# NANO33BLE_SENSE.net
KiCad netlist of a schematic drawn in Altium Designer
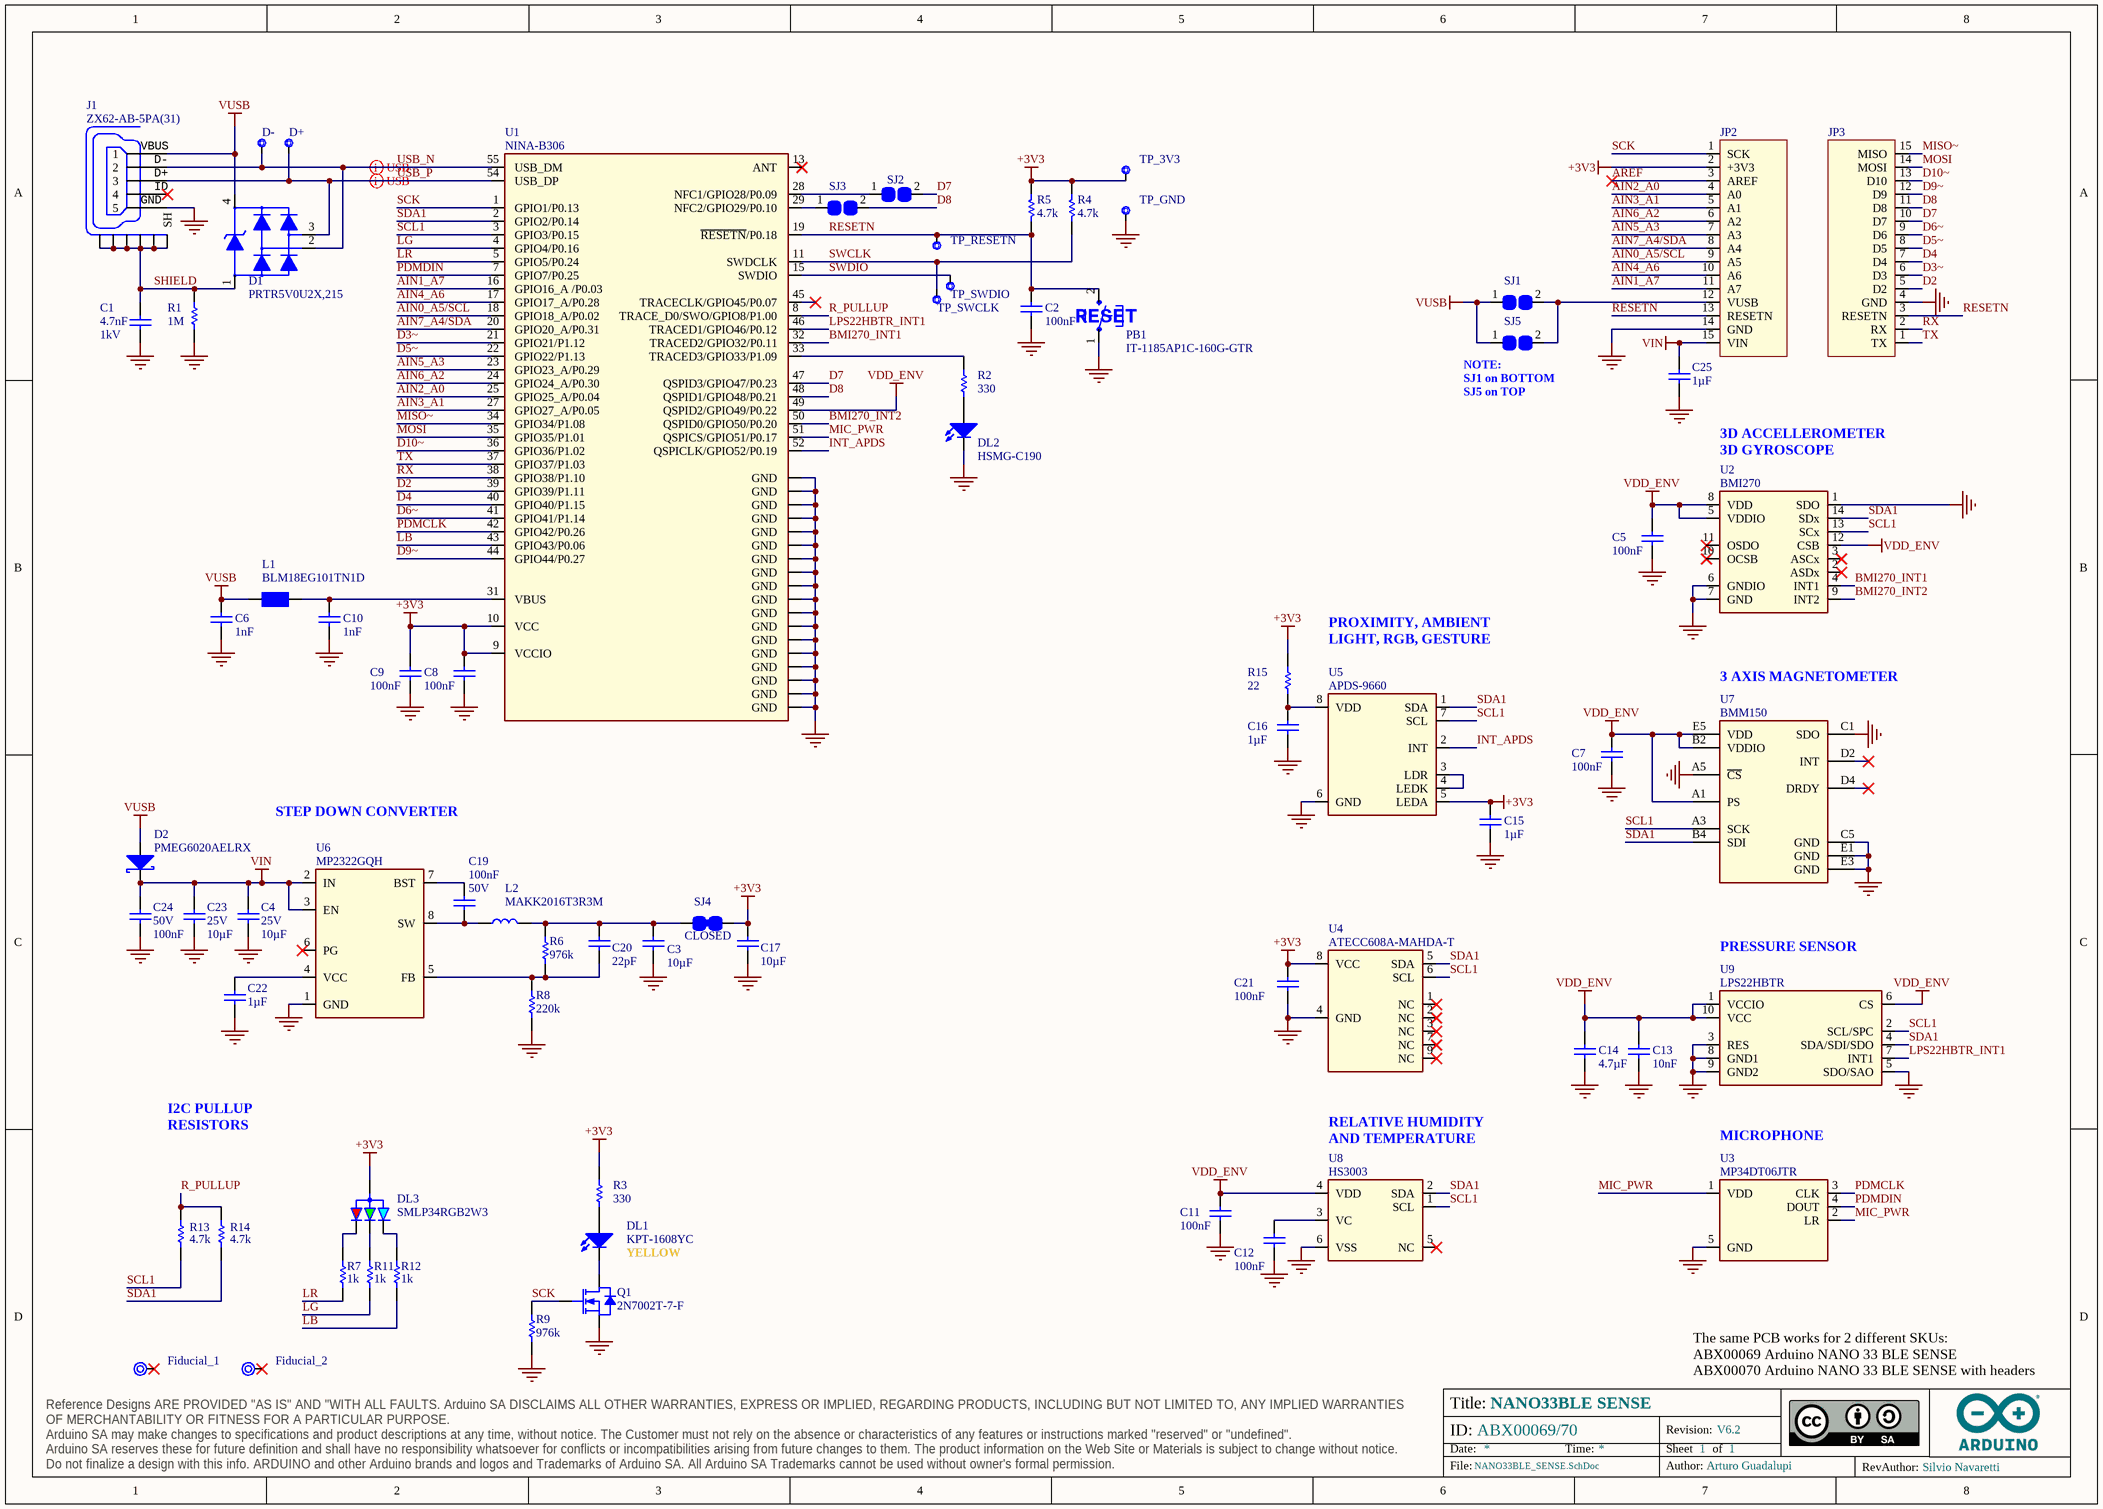
[diagram p0: NANO33BLE_SENSE.SchDoc]

(export (version "E")
  (design (tool "Eeschema 10.0.6"))
  (components
    (comp (ref "C1")
      (value "4.7nF")
      (footprint "CAP-0805")
      (description "CAP CHIP 0805 4.7nF 1000V X7R 10%")
      (fields
        (field (name "MANUFACTURER") "KEMET")
        (field (name "VOLTAGE") "1kV")
        (field (name "TOLERANCE") "10%")
      )
      (libsource (lib "Clean") (part "CAP"))
    )
    (comp (ref "C2")
      (value "100nF")
      (footprint "CAP-0402")
      (description "CAP CHIP 0402 100nF 50V X5R 10%")
      (fields (field (name "MANUFACTURER") "Murata") (field (name "PART NUMBER") "GRM155R61H104KE19D"))
      (libsource (lib "Clean") (part "CAP"))
    )
    (comp (ref "C3")
      (value "10µF")
      (footprint "CAP-0603")
      (description "CAP CHIP 0603 10uF 25V X5R 20%")
      (fields (field (name "VOLTAGE") "25V") (field (name "PART NUMBER") "GRM188R61E106MA73J"))
      (libsource (lib "Clean") (part "CAP"))
    )
    (comp (ref "C4")
      (value "10µF")
      (footprint "CAP-0603")
      (description "CAP CHIP 0603 10uF 25V X5R 20%")
      (fields
        (field (name "VOLTAGE") "25V")
        (field (name "PART NUMBER") "GRM188R61E106MA73J")
        (field (name "TOLERANCE") "20%")
      )
      (libsource (lib "Clean") (part "CAP"))
    )
    (comp (ref "C5")
      (value "100nF")
      (footprint "CAP-0402")
      (description "CAP CHIP 0402 100nF 16V X7R 10%")
      (fields (field (name "MANUFACTURER") "KEMET") (field (name "PART NUMBER") "C0402C104K4RACTU"))
      (libsource (lib "Clean") (part "CAP"))
    )
    (comp (ref "C6")
      (value "1nF")
      (footprint "CAP-0402")
      (description "CAP CHIP 0402 1nF 50V X7R 10%")
      (fields (field (name "MANUFACTURER") "KEMET") (field (name "PART NUMBER") "C0402C100K5RACTU"))
      (libsource (lib "Clean") (part "CAP"))
    )
    (comp (ref "C7")
      (value "100nF")
      (footprint "CAP-0402")
      (description "CAP CHIP 0402 100nF 50V X5R 10%")
      (fields (field (name "VOLTAGE") "50V") (field (name "TOLERANCE") "10%"))
      (libsource (lib "Clean") (part "CAP"))
    )
    (comp (ref "C8")
      (value "100nF")
      (footprint "CAP-0402")
      (description "CAP CHIP 0402 100nF 50V X5R 10%")
      (fields (field (name "MANUFACTURER") "Murata") (field (name "PART NUMBER") "GRM155R61H104KE19D"))
      (libsource (lib "Clean") (part "CAP"))
    )
    (comp (ref "C9")
      (value "100nF")
      (footprint "CAP-0402")
      (description "CAP CHIP 0402 100nF 50V X5R 10%")
      (fields (field (name "MANUFACTURER") "Murata") (field (name "PART NUMBER") "GRM155R61H104KE19D"))
      (libsource (lib "Clean") (part "CAP"))
    )
    (comp (ref "C10")
      (value "1nF")
      (footprint "CAP-0402")
      (description "CAP CHIP 0402 1nF 50V X7R 10%")
      (fields (field (name "MANUFACTURER") "KEMET") (field (name "PART NUMBER") "C0402C100K5RACTU"))
      (libsource (lib "Clean") (part "CAP"))
    )
    (comp (ref "C11")
      (value "100nF")
      (footprint "CAP-0402")
      (description "CAP CHIP 0402 100nF 50V X5R 10%")
      (fields (field (name "MANUFACTURER") "Murata") (field (name "PART NUMBER") "GRM155R61H104KE19D"))
      (libsource (lib "Clean") (part "CAP"))
    )
    (comp (ref "C12")
      (value "100nF")
      (footprint "CAP-0402")
      (description "CAP CHIP 0402 100nF 50V X5R 10%")
      (fields (field (name "MANUFACTURER") "Murata") (field (name "PART NUMBER") "GRM155R61H104KE19D"))
      (libsource (lib "Clean") (part "CAP"))
    )
    (comp (ref "C13")
      (value "10nF")
      (footprint "CAP-0402")
      (description "CAP CHIP 0402 10nF 50V X7R 10%")
      (fields (field (name "MANUFACTURER") "KEMET") (field (name "VOLTAGE") "50V"))
      (libsource (lib "Clean") (part "CAP"))
    )
    (comp (ref "C14")
      (value "4.7µF")
      (footprint "CAP-0402")
      (description "CAP CHIP 0402 4.7uF 6V3 X5R 20%")
      (fields (field (name "MANUFACTURER") "Murata") (field (name "PART NUMBER") "GRM155R60J475ME47D"))
      (libsource (lib "Clean") (part "CAP"))
    )
    (comp (ref "C15")
      (value "1µF")
      (footprint "CAP-0402")
      (description "CAP CHIP 0402 1uF 10V X5R 10%")
      (fields (field (name "MANUFACTURER") "KEMET") (field (name "VOLTAGE") "10V"))
      (libsource (lib "Clean") (part "CAP"))
    )
    (comp (ref "C16")
      (value "1µF")
      (footprint "CAP-0402")
      (description "CAP CHIP 0402 1uF 10V X5R 10%")
      (fields (field (name "MANUFACTURER") "KEMET") (field (name "VOLTAGE") "10V"))
      (libsource (lib "Clean") (part "CAP"))
    )
    (comp (ref "C17")
      (value "10µF")
      (footprint "CAP-0603")
      (description "CAP CHIP 0603 10uF 25V X5R 20%")
      (fields (field (name "VOLTAGE") "25V") (field (name "PART NUMBER") "GRM188R61E106MA73J"))
      (libsource (lib "Clean") (part "CAP"))
    )
    (comp (ref "C19")
      (value "100nF")
      (footprint "CAP-0402")
      (description "CAP CHIP 0402 100nF 50V X5R 10%")
      (fields
        (field (name "VOLTAGE") "50V")
        (field (name "PART NUMBER") "GRM155R61H104KE19D")
        (field (name "MANUFACTURER") "Murata")
      )
      (libsource (lib "Clean") (part "CAP"))
    )
    (comp (ref "C20")
      (value "22pF")
      (footprint "CAP-0402")
      (description "CAP CHIP 0402 22pF 50V C0G 5%")
      (fields (field (name "TOLERANCE") "5%") (field (name "PART NUMBER") "C0402C220J5GAC7411"))
      (libsource (lib "Clean") (part "CAP"))
    )
    (comp (ref "C21")
      (value "100nF")
      (footprint "CAP-0402")
      (description "CAP CHIP 0402 100nF 50V X5R 10%")
      (fields (field (name "MANUFACTURER") "Murata") (field (name "PART NUMBER") "GRM155R61H104KE19D"))
      (libsource (lib "Clean") (part "CAP"))
    )
    (comp (ref "C22")
      (value "1µF")
      (footprint "CAP-0402")
      (description "CAP CHIP 0402 1uF 10V X5R 10%")
      (fields (field (name "TOLERANCE") "10%") (field (name "MANUFACTURER") "KEMET"))
      (libsource (lib "Clean") (part "CAP"))
    )
    (comp (ref "C23")
      (value "10µF")
      (footprint "CAP-0603")
      (description "CAP CHIP 0603 10uF 25V X5R 20%")
      (fields
        (field (name "VOLTAGE") "25V")
        (field (name "PART NUMBER") "GRM188R61E106MA73J")
        (field (name "TOLERANCE") "20%")
      )
      (libsource (lib "Clean") (part "CAP"))
    )
    (comp (ref "C24")
      (value "100nF")
      (footprint "CAP-0402")
      (description "CAP CHIP 0402 100nF 50V X5R 10%")
      (fields
        (field (name "MANUFACTURER") "Murata")
        (field (name "PART NUMBER") "GRM155R61H104KE19D")
        (field (name "VOLTAGE") "50V")
      )
      (libsource (lib "Clean") (part "CAP"))
    )
    (comp (ref "C25")
      (value "1µF")
      (footprint "CAP-0402")
      (description "CAP CHIP 0402 1uF 10V X5R 10%")
      (fields (field (name "MANUFACTURER") "KEMET") (field (name "PART NUMBER") "C0402C105K8PACTU"))
      (libsource (lib "Clean") (part "CAP"))
    )
    (comp (ref "D+")
      (value "CMP-018-0005-A.3")
      (footprint "TP-1.00MM")
      (description "Test point 1.00mm")
      (libsource (lib "Clean") (part "TESTPOINT"))
    )
    (comp (ref "D-")
      (value "CMP-018-0005-A.3")
      (footprint "TP-1.00MM")
      (description "Test point 1.00mm")
      (libsource (lib "Clean") (part "TESTPOINT"))
    )
    (comp (ref "D1")
      (value "PRTR5V0U2X,215")
      (footprint "SOT190P230X110-4N")
      (description "TVS ARRAY 4LIN.8kV 1pF SOT143B")
      (fields (field (name "MANUFACTURER") "Nexperia"))
      (libsource (lib "Clean") (part "PRTR5V0U2X,215"))
    )
    (comp (ref "D2")
      (value "PMEG6020AELRX")
      (footprint "SOD123-1")
      (description "DIODE SCHOTTKY SMD 2A 60V SOD123FL")
      (fields (field (name "MANUFACTURER") "Nexperia"))
      (libsource (lib "Clean") (part "PMEG6020AELRX"))
    )
    (comp (ref "DL1")
      (value "KPT-1608YC")
      (footprint "LEDC1608X80N-AK")
      (description "LED SMD 0603 GIA588   8mcd 120^")
      (fields (field (name "MANUFACTURER") "Kingbright"))
      (libsource (lib "Clean") (part "LED"))
    )
    (comp (ref "DL2")
      (value "HSMG-C190")
      (footprint "LEDC1608X80N-AK")
      (description "LED SMD 0603 GREEN/568 15mcd 120^")
      (fields (field (name "MANUFACTURER") "Broadcom"))
      (libsource (lib "Clean") (part "LED"))
    )
    (comp (ref "DL3")
      (value "SMLP34RGB2W3")
      (footprint "SMLP34RGB2W")
      (description "LED RGB DIFFUSED PICOLED SMD")
      (fields (field (name "MANUFACTURER") "ROHM Semiconductor"))
      (libsource (lib "Clean") (part "SMLP34RGB2W3"))
    )
    (comp (ref "Fiducial_1")
      (value "Fiducial mark 1mm with 2mm solder")
      (footprint "Fiducial mark 1mm with circle-Footprint-1")
      (libsource (lib "Clean") (part "Fiducial mark 1mm with circle"))
    )
    (comp (ref "Fiducial_2")
      (value "Fiducial mark 1mm with 2mm solder")
      (footprint "Fiducial mark 1mm with circle-Footprint-1")
      (libsource (lib "Clean") (part "Fiducial mark 1mm with circle"))
    )
    (comp (ref "J1")
      (value "ZX62-AB-5PA(31)")
      (footprint "ZX62-AB-5PA")
      (description "CONN USB MICRO F/90^ SMD TipoAB 5x1")
      (fields (field (name "MANUFACTURER") "Hirose"))
      (libsource (lib "Clean") (part "ZX62-AB-5PA(31)"))
    )
    (comp (ref "JP2")
      (value "PINHD-1X15-NANO-ANALOG-CASTELLATED")
      (footprint "PINHD-1X14_5VF")
      (description "CONN THD SOCKET F/1/D 15V JANALOG NANO-TYPE CASTELLATED")
      (libsource (lib "Clean") (part "PINHD-1X15-NANO-ANALOG-CASTELLATED"))
    )
    (comp (ref "JP3")
      (value "PINHD-1X15-NANO-DIGITAL")
      (footprint "PINHD-1X14_5VF")
      (description "CONN THD SOCKET F/1/D 15V JDIGITAL NANO-TYPE CASTELLATED")
      (libsource (lib "Clean") (part "PINHD-1X15-NANO-DIGITAL"))
    )
    (comp (ref "L1")
      (value "BLM18EG101TN1D")
      (footprint "L-0603")
      (description "FERRITE SMD 0603 45mOHM 2A")
      (fields
        (field (name "MANUFACTURER") "Murata")
        (field (name "PART NUMBER") "BLM18EG101TN1D")
        (field (name "TOLERANCE") "25%")
      )
      (libsource (lib "Clean") (part "Ferrite"))
    )
    (comp (ref "L2")
      (value "MAKK2016T3R3M")
      (footprint "MAKK2016T3R3M-Footprint-1")
      (description "IND CHIP 0806 3.3 uH 20% 1.2A")
      (fields (field (name "TOLERANCE") "20%") (field (name "MANUFACTURER") "Taiyo Yuden"))
      (libsource (lib "Clean") (part "Inductor"))
    )
    (comp (ref "PB1")
      (value "IT-1185AP1C-160G-GTR")
      (footprint "C&K_PTS820_NO_HOLES-1")
      (description "PUSHBUTTON WHITE NO ANCHORS")
      (fields (field (name "MANUFACTURER") "Switronic"))
      (libsource (lib "Clean") (part "PTS820"))
    )
    (comp (ref "Q1")
      (value "2N7002T-7-F")
      (footprint "SOT523")
      (description "MOSFET N-CH 60V 115mA SOT523")
      (fields (field (name "MANUFACTURER") "Diodes Inc."))
      (libsource (lib "Clean") (part "NMOS"))
    )
    (comp (ref "R1")
      (value "1M")
      (footprint "RES-0402")
      (description "RES CHIP 0402 1M 1% 1/16W")
      (fields (field (name "MANUFACTURER") "Vishay") (field (name "POWER") "63mW"))
      (libsource (lib "Clean") (part "RES"))
    )
    (comp (ref "R2")
      (value "330")
      (footprint "RES-0402")
      (description "RES CHIP 0402 330R 5% 1/16W")
      (fields (field (name "MANUFACTURER") "Vishay") (field (name "POWER") "63mW"))
      (libsource (lib "Clean") (part "RES"))
    )
    (comp (ref "R3")
      (value "330")
      (footprint "RES-0402")
      (description "RES CHIP 0402 330R 5% 1/16W")
      (fields (field (name "MANUFACTURER") "Vishay") (field (name "POWER") "63mW"))
      (libsource (lib "Clean") (part "RES"))
    )
    (comp (ref "R4")
      (value "4.7k")
      (footprint "RES-0402")
      (description "RES CHIP 0402 4K7 1% 1/16W")
      (fields (field (name "MANUFACTURER") "Yageo") (field (name "PART NUMBER") "RC0402FR-074K7L"))
      (libsource (lib "Clean") (part "RES"))
    )
    (comp (ref "R5")
      (value "4.7k")
      (footprint "RES-0402")
      (description "RES CHIP 0402 4K7 1% 1/16W")
      (fields (field (name "MANUFACTURER") "Yageo") (field (name "PART NUMBER") "RC0402FR-074K7L"))
      (libsource (lib "Clean") (part "RES"))
    )
    (comp (ref "R6")
      (value "976k")
      (footprint "RES-0402")
      (description "RES CHIP 0402 976K 1% 1/16W")
      (fields (field (name "TOLERANCE") "1%") (field (name "POWER") "63mW"))
      (libsource (lib "Clean") (part "RES"))
    )
    (comp (ref "R7")
      (value "1k")
      (footprint "RES-0402")
      (description "RES CHIP 0402 1K 1% 1/16W")
      (fields (field (name "MANUFACTURER") "Vishay") (field (name "POWER") "63mW"))
      (libsource (lib "Clean") (part "RES"))
    )
    (comp (ref "R8")
      (value "220k")
      (footprint "RES-0402")
      (description "RES CHIP 0402 220K 1% 1/16W")
      (fields (field (name "MANUFACTURER") "Vishay") (field (name "PART NUMBER") "CRCW0402220KFKED"))
      (libsource (lib "Clean") (part "RES"))
    )
    (comp (ref "R9")
      (value "976k")
      (footprint "RES-0402")
      (description "RES CHIP 0402 976K 1% 1/16W")
      (fields (field (name "TOLERANCE") "1%") (field (name "POWER") "63mW"))
      (libsource (lib "Clean") (part "RES"))
    )
    (comp (ref "R11")
      (value "1k")
      (footprint "RES-0402")
      (description "RES CHIP 0402 1K 1% 1/16W")
      (fields (field (name "MANUFACTURER") "Vishay") (field (name "POWER") "63mW"))
      (libsource (lib "Clean") (part "RES"))
    )
    (comp (ref "R12")
      (value "1k")
      (footprint "RES-0402")
      (description "RES CHIP 0402 1K 1% 1/16W")
      (fields (field (name "MANUFACTURER") "Vishay") (field (name "POWER") "63mW"))
      (libsource (lib "Clean") (part "RES"))
    )
    (comp (ref "R13")
      (value "4.7k")
      (footprint "RES-0402")
      (description "RES CHIP 0402 4K7 1% 1/16W")
      (fields (field (name "MANUFACTURER") "Yageo") (field (name "PART NUMBER") "RC0402FR-074K7L"))
      (libsource (lib "Clean") (part "RES"))
    )
    (comp (ref "R14")
      (value "4.7k")
      (footprint "RES-0402")
      (description "RES CHIP 0402 4K7 1% 1/16W")
      (fields (field (name "MANUFACTURER") "Yageo") (field (name "PART NUMBER") "RC0402FR-074K7L"))
      (libsource (lib "Clean") (part "RES"))
    )
    (comp (ref "R15")
      (value "22")
      (footprint "RES-0402")
      (description "RES CHIP 0402 22R 1% 1/16W")
      (fields (field (name "MANUFACTURER") "Yageo") (field (name "TOLERANCE") "1%"))
      (libsource (lib "Clean") (part "RES"))
    )
    (comp (ref "SJ1")
      (value "SMD solder JUMPER 0805")
      (footprint "SJ")
      (description "Solder Jumper 0805 THIS IS NOT A COMPONENT")
      (libsource (lib "Clean") (part "SJ"))
    )
    (comp (ref "SJ2")
      (value "SMD solder JUMPER 0805")
      (footprint "SJ")
      (description "Solder Jumper 0805 THIS IS NOT A COMPONENT")
      (libsource (lib "Clean") (part "SJ"))
    )
    (comp (ref "SJ3")
      (value "SMD solder JUMPER 0805")
      (footprint "SJ")
      (description "Solder Jumper 0805 THIS IS NOT A COMPONENT")
      (libsource (lib "Clean") (part "SJ"))
    )
    (comp (ref "SJ4")
      (value "SMD solder JUMPER CLOSED")
      (footprint "SJ")
      (description "Solder Jumper shorted pads. This is not a component")
      (libsource (lib "Clean") (part "CLOSED"))
    )
    (comp (ref "SJ5")
      (value "SMD solder JUMPER 0805")
      (footprint "SJ")
      (description "Solder Jumper 0805 THIS IS NOT A COMPONENT")
      (libsource (lib "Clean") (part "SJ"))
    )
    (comp (ref "TP_3V3")
      (value "CMP-018-0005-A.3")
      (footprint "TP-1.00MM")
      (description "Test point 1.00mm")
      (libsource (lib "Clean") (part "TESTPOINT"))
    )
    (comp (ref "TP_GND")
      (value "CMP-018-0005-A.3")
      (footprint "TP-1.00MM")
      (description "Test point 1.00mm")
      (libsource (lib "Clean") (part "TESTPOINT"))
    )
    (comp (ref "TP_RESETN")
      (value "CMP-018-0005-A.3")
      (footprint "TP-1.00MM")
      (description "Test point 1.00mm")
      (libsource (lib "Clean") (part "TESTPOINT"))
    )
    (comp (ref "TP_SWCLK")
      (value "CMP-018-0005-A.3")
      (footprint "TP-1.00MM")
      (description "Test point 1.00mm")
      (libsource (lib "Clean") (part "TESTPOINT"))
    )
    (comp (ref "TP_SWDIO")
      (value "CMP-018-0005-A.3")
      (footprint "TP-1.00MM")
      (description "Test point 1.00mm")
      (libsource (lib "Clean") (part "TESTPOINT"))
    )
    (comp (ref "U1")
      (value "NINA-B306")
      (footprint "NINA-B3X")
      (description "MODULE BLE 5.0 STAND ALONE nRF52")
      (fields (field (name "MANUFACTURER") "UBlox"))
      (libsource (lib "Clean") (part "NINA-B306-Symbol-1"))
    )
    (comp (ref "U2")
      (value "BMI270")
      (footprint "VFLGA14")
      (description "IC IMU 6 AXIS 14VFLGA pin to pin alternative to LSM6DSOXTR")
      (fields (field (name "MANUFACTURER") "Bosch Sensortech"))
      (libsource (lib "Clean") (part "BMI270-Symbol-1"))
    )
    (comp (ref "U3")
      (value "MP34DT06JTR")
      (footprint "HCLGA")
      (description "SENS MEMS AUDIO OMNIDIRECTIONAL")
      (fields (field (name "MANUFACTURER") "STMicroelectronics"))
      (libsource (lib "Clean") (part "MP34DT06JTR"))
    )
    (comp (ref "U4")
      (value "ATECC608A-MAHDA-T")
      (footprint "UDFN8")
      (description "IC AUTHENTICATION CHIP UDFN8")
      (fields (field (name "MANUFACTURER") "Microchip"))
      (libsource (lib "Clean") (part "ATECC608A-MAHDA-T"))
    )
    (comp (ref "U5")
      (value "APDS-9660")
      (footprint "APDS-9660-Footprint-1")
      (description "IC SENS OPT 560NM AMBIENT MODULE APDS-9960")
      (fields (field (name "MANUFACTURER") "Broadcom"))
      (libsource (lib "Clean") (part "APDS-9660"))
    )
    (comp (ref "U6")
      (value "MP2322GQH")
      (footprint "QFN50P150X200X90-8L")
      (description "IC STEP DOWN CONV 1A 22V QFN8")
      (fields (field (name "MANUFACTURER") "Monolithic Power Systems"))
      (libsource (lib "Clean") (part "MP2322GQH"))
    )
    (comp (ref "U7")
      (value "BMM150")
      (footprint "FP-BMM150-MFG")
      (description "IC SENSOR 3-AXIS GEOMAGNETIC")
      (fields (field (name "MANUFACTURER") "Bosch Sensortec"))
      (libsource (lib "Clean") (part "24d48050165bead51c97f0d4a59b4f7"))
    )
    (comp (ref "U8")
      (value "HS3003")
      (footprint "HS3003-Footprint-1")
      (description "IC PRESSURE AND TEMPERATURE SENSOR 6-LGA")
      (fields (field (name "MANUFACTURER") "Renesas"))
      (libsource (lib "Clean") (part "HS3003-Symbol-1"))
    )
    (comp (ref "U9")
      (value "LPS22HBTR")
      (footprint "LPS22H")
      (description "SENSOR PRESSURE 3.77 PSI ~ 18.27 PSI (26 kPa ~ 126 kPa) Absolute 24 b 10-WFLGA")
      (fields (field (name "MANUFACTURER") "STMicroelectronics"))
      (libsource (lib "Clean") (part "LPS22HBTR"))
    )
  )
  (nets
    (net (code "1") (name "+3V3") (class "Default")
      (node (ref "C15") (pin "2") (pinfunction "2_2") (pintype "passive"))
      (node (ref "C17") (pin "2") (pinfunction "2_2") (pintype "passive"))
      (node (ref "C21") (pin "2") (pinfunction "2_2") (pintype "passive"))
      (node (ref "C8") (pin "2") (pinfunction "2_2") (pintype "passive"))
      (node (ref "C9") (pin "1") (pinfunction "1_1") (pintype "passive"))
      (node (ref "DL3") (pin "1") (pinfunction "ANODE_1") (pintype "passive"))
      (node (ref "JP2") (pin "2") (pinfunction "+3V3_2") (pintype "passive"))
      (node (ref "R15") (pin "2") (pinfunction "2_2") (pintype "passive"))
      (node (ref "R3") (pin "2") (pinfunction "2_2") (pintype "passive"))
      (node (ref "R4") (pin "2") (pinfunction "2_2") (pintype "passive"))
      (node (ref "R5") (pin "2") (pinfunction "2_2") (pintype "passive"))
      (node (ref "SJ4") (pin "2") (pinfunction "2_2") (pintype "passive"))
      (node (ref "TP_3V3") (pin "X") (pinfunction "X_X") (pintype "passive"))
      (node (ref "U1") (pin "10") (pinfunction "VCC_10") (pintype "power_in"))
      (node (ref "U1") (pin "9") (pinfunction "VCCIO_9") (pintype "power_in"))
      (node (ref "U4") (pin "8") (pinfunction "VCC_8") (pintype "passive"))
      (node (ref "U5") (pin "5") (pinfunction "LEDA_5") (pintype "passive"))
    )
    (net (code "2") (name "/AIN0_A5{slash}SCL") (class "Default")
      (node (ref "JP2") (pin "9") (pinfunction "A5_9") (pintype "passive"))
      (node (ref "U1") (pin "18") (pinfunction "GPIO18_A/P0.02_18") (pintype "passive"))
    )
    (net (code "3") (name "/AIN1_A7") (class "Default")
      (node (ref "JP2") (pin "11") (pinfunction "A7_11") (pintype "passive"))
      (node (ref "U1") (pin "16") (pinfunction "GPIO16_A_/P0.03_16") (pintype "passive"))
    )
    (net (code "4") (name "/AIN2_A0") (class "Default")
      (node (ref "JP2") (pin "4") (pinfunction "A0_4") (pintype "passive"))
      (node (ref "U1") (pin "25") (pinfunction "GPIO25_A/P0.04_25") (pintype "passive"))
    )
    (net (code "5") (name "/AIN3_A1") (class "Default")
      (node (ref "JP2") (pin "5") (pinfunction "A1_5") (pintype "passive"))
      (node (ref "U1") (pin "27") (pinfunction "GPIO27_A/P0.05_27") (pintype "passive"))
    )
    (net (code "6") (name "/AIN4_A6") (class "Default")
      (node (ref "JP2") (pin "10") (pinfunction "A6_10") (pintype "passive"))
      (node (ref "U1") (pin "17") (pinfunction "GPIO17_A/P0.28_17") (pintype "passive"))
    )
    (net (code "7") (name "/AIN5_A3") (class "Default")
      (node (ref "JP2") (pin "7") (pinfunction "A3_7") (pintype "passive"))
      (node (ref "U1") (pin "23") (pinfunction "GPIO23_A/P0.29_23") (pintype "passive"))
    )
    (net (code "8") (name "/AIN6_A2") (class "Default")
      (node (ref "JP2") (pin "6") (pinfunction "A2_6") (pintype "passive"))
      (node (ref "U1") (pin "24") (pinfunction "GPIO24_A/P0.30_24") (pintype "passive"))
    )
    (net (code "9") (name "/AIN7_A4{slash}SDA") (class "Default")
      (node (ref "JP2") (pin "8") (pinfunction "A4_8") (pintype "passive"))
      (node (ref "U1") (pin "20") (pinfunction "GPIO20_A/P0.31_20") (pintype "passive"))
    )
    (net (code "10") (name "/AREF") (class "Default")
      (node (ref "JP2") (pin "3") (pinfunction "AREF_3") (pintype "passive+no_connect"))
    )
    (net (code "11") (name "/BMI270_INT1") (class "Default")
      (node (ref "U1") (pin "32") (pinfunction "TRACED2/GPIO32/P0.11_32") (pintype "passive"))
      (node (ref "U2") (pin "4") (pinfunction "INT1_4") (pintype "passive"))
    )
    (net (code "12") (name "/BMI270_INT2") (class "Default")
      (node (ref "U1") (pin "50") (pinfunction "QSPID0/GPIO50/P0.20_50") (pintype "passive"))
      (node (ref "U2") (pin "9") (pinfunction "INT2_9") (pintype "passive"))
    )
    (net (code "13") (name "/D2") (class "Default")
      (node (ref "JP3") (pin "5") (pinfunction "D2_5") (pintype "passive"))
      (node (ref "U1") (pin "39") (pinfunction "GPIO39/P1.11_39") (pintype "passive"))
    )
    (net (code "14") (name "/D3~") (class "Default")
      (node (ref "JP3") (pin "6") (pinfunction "D3_6") (pintype "passive"))
      (node (ref "U1") (pin "21") (pinfunction "GPIO21/P1.12_21") (pintype "passive"))
    )
    (net (code "15") (name "/D4") (class "Default")
      (node (ref "JP3") (pin "7") (pinfunction "D4_7") (pintype "passive"))
      (node (ref "U1") (pin "40") (pinfunction "GPIO40/P1.15_40") (pintype "passive"))
    )
    (net (code "16") (name "/D5~") (class "Default")
      (node (ref "JP3") (pin "8") (pinfunction "D5_8") (pintype "passive"))
      (node (ref "U1") (pin "22") (pinfunction "GPIO22/P1.13_22") (pintype "passive"))
    )
    (net (code "17") (name "/D6~") (class "Default")
      (node (ref "JP3") (pin "9") (pinfunction "D6_9") (pintype "passive"))
      (node (ref "U1") (pin "41") (pinfunction "GPIO41/P1.14_41") (pintype "passive"))
    )
    (net (code "18") (name "/D7") (class "Default")
      (node (ref "JP3") (pin "10") (pinfunction "D7_10") (pintype "passive"))
      (node (ref "SJ2") (pin "2") (pinfunction "2_2") (pintype "passive"))
      (node (ref "U1") (pin "47") (pinfunction "QSPID3/GPIO47/P0.23_47") (pintype "passive"))
    )
    (net (code "19") (name "/D8") (class "Default")
      (node (ref "JP3") (pin "11") (pinfunction "D8_11") (pintype "passive"))
      (node (ref "SJ3") (pin "2") (pinfunction "2_2") (pintype "passive"))
      (node (ref "U1") (pin "48") (pinfunction "QSPID1/GPIO48/P0.21_48") (pintype "passive"))
    )
    (net (code "20") (name "/D9~") (class "Default")
      (node (ref "JP3") (pin "12") (pinfunction "D9_12") (pintype "passive"))
      (node (ref "U1") (pin "44") (pinfunction "GPIO44/P0.27_44") (pintype "passive"))
    )
    (net (code "21") (name "/D10~") (class "Default")
      (node (ref "JP3") (pin "13") (pinfunction "D10_13") (pintype "passive"))
      (node (ref "U1") (pin "36") (pinfunction "GPIO36/P1.02_36") (pintype "passive"))
    )
    (net (code "22") (name "/INT_APDS") (class "Default")
      (node (ref "U1") (pin "52") (pinfunction "QSPICLK/GPIO52/P0.19_52") (pintype "passive"))
      (node (ref "U5") (pin "2") (pinfunction "INT_2") (pintype "passive"))
    )
    (net (code "23") (name "/LB") (class "Default")
      (node (ref "R12") (pin "1") (pinfunction "1_1") (pintype "passive"))
      (node (ref "U1") (pin "43") (pinfunction "GPIO43/P0.06_43") (pintype "passive"))
    )
    (net (code "24") (name "/LG") (class "Default")
      (node (ref "R11") (pin "1") (pinfunction "1_1") (pintype "passive"))
      (node (ref "U1") (pin "4") (pinfunction "GPIO4/P0.16_4") (pintype "passive"))
    )
    (net (code "25") (name "/LPS22HBTR_INT1") (class "Default")
      (node (ref "U1") (pin "46") (pinfunction "TRACED1/GPIO46/P0.12_46") (pintype "passive"))
      (node (ref "U9") (pin "7") (pinfunction "INT1_7") (pintype "passive"))
    )
    (net (code "26") (name "/LR") (class "Default")
      (node (ref "R7") (pin "1") (pinfunction "1_1") (pintype "passive"))
      (node (ref "U1") (pin "5") (pinfunction "GPIO5/P0.24_5") (pintype "passive"))
    )
    (net (code "27") (name "/MIC_PWR") (class "Default")
      (node (ref "U1") (pin "51") (pinfunction "QSPICS/GPIO51/P0.17_51") (pintype "passive"))
      (node (ref "U3") (pin "1") (pinfunction "VDD_1") (pintype "power_in"))
      (node (ref "U3") (pin "2") (pinfunction "LR_2") (pintype "passive"))
    )
    (net (code "28") (name "/MISO~") (class "Default")
      (node (ref "JP3") (pin "15") (pinfunction "MISO_15") (pintype "passive"))
      (node (ref "U1") (pin "34") (pinfunction "GPIO34/P1.08_34") (pintype "passive"))
    )
    (net (code "29") (name "/MOSI") (class "Default")
      (node (ref "JP3") (pin "14") (pinfunction "MOSI_14") (pintype "passive"))
      (node (ref "U1") (pin "35") (pinfunction "GPIO35/P1.01_35") (pintype "passive"))
    )
    (net (code "30") (name "/PDMCLK") (class "Default")
      (node (ref "U1") (pin "42") (pinfunction "GPIO42/P0.26_42") (pintype "passive"))
      (node (ref "U3") (pin "3") (pinfunction "CLK_3") (pintype "passive"))
    )
    (net (code "31") (name "/PDMDIN") (class "Default")
      (node (ref "U1") (pin "7") (pinfunction "GPIO7/P0.25_7") (pintype "passive"))
      (node (ref "U3") (pin "4") (pinfunction "DOUT_4") (pintype "passive"))
    )
    (net (code "32") (name "/RESETN") (class "Default")
      (node (ref "C2") (pin "1") (pinfunction "1_1") (pintype "passive"))
      (node (ref "JP2") (pin "13") (pinfunction "RESETN_13") (pintype "passive"))
      (node (ref "JP3") (pin "3") (pinfunction "RESETN_3") (pintype "passive"))
      (node (ref "PB1") (pin "2") (pinfunction "2_2") (pintype "passive"))
      (node (ref "R5") (pin "1") (pinfunction "1_1") (pintype "passive"))
      (node (ref "TP_RESETN") (pin "X") (pinfunction "X_X") (pintype "passive"))
      (node (ref "U1") (pin "19") (pinfunction "~{RESETN}/P0.18_19") (pintype "passive"))
    )
    (net (code "33") (name "/RX") (class "Default")
      (node (ref "JP3") (pin "2") (pinfunction "RX_2") (pintype "passive"))
      (node (ref "U1") (pin "38") (pinfunction "GPIO38/P1.10_38") (pintype "passive"))
    )
    (net (code "34") (name "/R_PULLUP") (class "Default")
      (node (ref "R13") (pin "2") (pinfunction "2_2") (pintype "passive"))
      (node (ref "R14") (pin "2") (pinfunction "2_2") (pintype "passive"))
      (node (ref "U1") (pin "8") (pinfunction "TRACE_D0/SWO/GPIO8/P1.00_8") (pintype "passive"))
    )
    (net (code "35") (name "/SCK") (class "Default")
      (node (ref "JP2") (pin "1") (pinfunction "SCK_1") (pintype "passive"))
      (node (ref "Q1") (pin "G") (pinfunction "G_G") (pintype "passive"))
      (node (ref "R9") (pin "2") (pinfunction "2_2") (pintype "passive"))
      (node (ref "U1") (pin "1") (pinfunction "GPIO1/P0.13_1") (pintype "passive"))
    )
    (net (code "36") (name "/SCL1") (class "Default")
      (node (ref "R13") (pin "1") (pinfunction "1_1") (pintype "passive"))
      (node (ref "U1") (pin "3") (pinfunction "GPIO3/P0.15_3") (pintype "passive"))
      (node (ref "U2") (pin "13") (pinfunction "SCx_13") (pintype "passive"))
      (node (ref "U4") (pin "6") (pinfunction "SCL_6") (pintype "passive"))
      (node (ref "U5") (pin "7") (pinfunction "SCL_7") (pintype "passive"))
      (node (ref "U7") (pin "A3") (pinfunction "SCK_A3") (pintype "passive"))
      (node (ref "U8") (pin "1") (pinfunction "SCL_1") (pintype "passive"))
      (node (ref "U9") (pin "2") (pinfunction "SCL/SPC_2") (pintype "passive"))
    )
    (net (code "37") (name "/SDA1") (class "Default")
      (node (ref "R14") (pin "1") (pinfunction "1_1") (pintype "passive"))
      (node (ref "U1") (pin "2") (pinfunction "GPIO2/P0.14_2") (pintype "passive"))
      (node (ref "U2") (pin "14") (pinfunction "SDx_14") (pintype "passive"))
      (node (ref "U4") (pin "5") (pinfunction "SDA_5") (pintype "passive"))
      (node (ref "U5") (pin "1") (pinfunction "SDA_1") (pintype "passive"))
      (node (ref "U7") (pin "B4") (pinfunction "SDI_B4") (pintype "passive"))
      (node (ref "U8") (pin "2") (pinfunction "SDA_2") (pintype "passive"))
      (node (ref "U9") (pin "4") (pinfunction "SDA/SDI/SDO_4") (pintype "passive"))
    )
    (net (code "38") (name "/SHIELD") (class "Default")
      (node (ref "C1") (pin "2") (pinfunction "2_2") (pintype "passive"))
      (node (ref "D1") (pin "1") (pinfunction "1_1") (pintype "passive"))
      (node (ref "J1") (pin "M1") (pinfunction "SH_M1") (pintype "passive"))
      (node (ref "J1") (pin "M2") (pinfunction "SH_M2") (pintype "passive"))
      (node (ref "J1") (pin "M3") (pinfunction "SH_M3") (pintype "passive"))
      (node (ref "J1") (pin "M4") (pinfunction "SH_M4") (pintype "passive"))
      (node (ref "J1") (pin "M5") (pinfunction "SH_M5") (pintype "passive"))
      (node (ref "J1") (pin "M6") (pinfunction "SH_M6") (pintype "passive"))
      (node (ref "R1") (pin "2") (pinfunction "2_2") (pintype "passive"))
    )
    (net (code "39") (name "/SWCLK") (class "Default")
      (node (ref "R4") (pin "1") (pinfunction "1_1") (pintype "passive"))
      (node (ref "TP_SWCLK") (pin "X") (pinfunction "X_X") (pintype "passive"))
      (node (ref "U1") (pin "11") (pinfunction "SWDCLK_11") (pintype "passive"))
    )
    (net (code "40") (name "/SWDIO") (class "Default")
      (node (ref "TP_SWDIO") (pin "X") (pinfunction "X_X") (pintype "passive"))
      (node (ref "U1") (pin "15") (pinfunction "SWDIO_15") (pintype "passive"))
    )
    (net (code "41") (name "/TX") (class "Default")
      (node (ref "JP3") (pin "1") (pinfunction "TX_1") (pintype "passive"))
      (node (ref "U1") (pin "37") (pinfunction "GPIO37/P1.03_37") (pintype "passive"))
    )
    (net (code "42") (name "/USB_N") (class "Default")
      (node (ref "D-") (pin "X") (pinfunction "X_X") (pintype "passive"))
      (node (ref "D1") (pin "2") (pinfunction "2_2") (pintype "passive"))
      (node (ref "J1") (pin "2") (pinfunction "2_2") (pintype "passive"))
      (node (ref "U1") (pin "55") (pinfunction "USB_DM_55") (pintype "passive"))
    )
    (net (code "43") (name "/USB_P") (class "Default")
      (node (ref "D+") (pin "X") (pinfunction "X_X") (pintype "passive"))
      (node (ref "D1") (pin "3") (pinfunction "3_3") (pintype "passive"))
      (node (ref "J1") (pin "3") (pinfunction "3_3") (pintype "passive"))
      (node (ref "U1") (pin "54") (pinfunction "USB_DP_54") (pintype "passive"))
    )
    (net (code "44") (name "GND") (class "Default")
      (node (ref "C1") (pin "1") (pinfunction "1_1") (pintype "passive"))
      (node (ref "C10") (pin "2") (pinfunction "2_2") (pintype "passive"))
      (node (ref "C11") (pin "2") (pinfunction "2_2") (pintype "passive"))
      (node (ref "C12") (pin "2") (pinfunction "2_2") (pintype "passive"))
      (node (ref "C13") (pin "2") (pinfunction "2_2") (pintype "passive"))
      (node (ref "C14") (pin "2") (pinfunction "2_2") (pintype "passive"))
      (node (ref "C15") (pin "1") (pinfunction "1_1") (pintype "passive"))
      (node (ref "C16") (pin "1") (pinfunction "1_1") (pintype "passive"))
      (node (ref "C17") (pin "1") (pinfunction "1_1") (pintype "passive"))
      (node (ref "C2") (pin "2") (pinfunction "2_2") (pintype "passive"))
      (node (ref "C21") (pin "1") (pinfunction "1_1") (pintype "passive"))
      (node (ref "C22") (pin "1") (pinfunction "1_1") (pintype "passive"))
      (node (ref "C23") (pin "1") (pinfunction "1_1") (pintype "passive"))
      (node (ref "C24") (pin "2") (pinfunction "2_2") (pintype "passive"))
      (node (ref "C25") (pin "1") (pinfunction "1_1") (pintype "passive"))
      (node (ref "C3") (pin "1") (pinfunction "1_1") (pintype "passive"))
      (node (ref "C4") (pin "1") (pinfunction "1_1") (pintype "passive"))
      (node (ref "C5") (pin "2") (pinfunction "2_2") (pintype "passive"))
      (node (ref "C6") (pin "2") (pinfunction "2_2") (pintype "passive"))
      (node (ref "C7") (pin "1") (pinfunction "1_1") (pintype "passive"))
      (node (ref "C8") (pin "1") (pinfunction "1_1") (pintype "passive"))
      (node (ref "C9") (pin "2") (pinfunction "2_2") (pintype "passive"))
      (node (ref "DL2") (pin "C") (pinfunction "C_C") (pintype "passive"))
      (node (ref "J1") (pin "5") (pinfunction "5_5") (pintype "passive"))
      (node (ref "JP2") (pin "14") (pinfunction "GND_14") (pintype "passive"))
      (node (ref "JP3") (pin "4") (pinfunction "GND_4") (pintype "passive"))
      (node (ref "PB1") (pin "1") (pinfunction "1_1") (pintype "passive"))
      (node (ref "Q1") (pin "S") (pinfunction "S_S") (pintype "passive"))
      (node (ref "R1") (pin "1") (pinfunction "1_1") (pintype "passive"))
      (node (ref "R8") (pin "1") (pinfunction "1_1") (pintype "passive"))
      (node (ref "R9") (pin "1") (pinfunction "1_1") (pintype "passive"))
      (node (ref "TP_GND") (pin "X") (pinfunction "X_X") (pintype "passive"))
      (node (ref "U1") (pin "12") (pinfunction "GND_12") (pintype "power_in"))
      (node (ref "U1") (pin "14") (pinfunction "GND_14") (pintype "power_in"))
      (node (ref "U1") (pin "26") (pinfunction "GND_26") (pintype "power_in"))
      (node (ref "U1") (pin "30") (pinfunction "GND_30") (pintype "power_in"))
      (node (ref "U1") (pin "53") (pinfunction "GND_53") (pintype "power_in"))
      (node (ref "U1") (pin "6") (pinfunction "GND_6") (pintype "power_in"))
      (node (ref "U1") (pin "GND1") (pinfunction "GND_GND1") (pintype "power_in"))
      (node (ref "U1") (pin "GND10") (pinfunction "GND_GND10") (pintype "power_in"))
      (node (ref "U1") (pin "GND11") (pinfunction "GND_GND11") (pintype "power_in"))
      (node (ref "U1") (pin "GND12") (pinfunction "GND_GND12") (pintype "power_in"))
      (node (ref "U1") (pin "GND2") (pinfunction "GND_GND2") (pintype "power_in"))
      (node (ref "U1") (pin "GND3") (pinfunction "GND_GND3") (pintype "power_in"))
      (node (ref "U1") (pin "GND4") (pinfunction "GND_GND4") (pintype "power_in"))
      (node (ref "U1") (pin "GND5") (pinfunction "GND_GND5") (pintype "power_in"))
      (node (ref "U1") (pin "GND6") (pinfunction "GND_GND6") (pintype "power_in"))
      (node (ref "U1") (pin "GND7") (pinfunction "GND_GND7") (pintype "power_in"))
      (node (ref "U1") (pin "GND8") (pinfunction "GND_GND8") (pintype "power_in"))
      (node (ref "U1") (pin "GND9") (pinfunction "GND_GND9") (pintype "power_in"))
      (node (ref "U2") (pin "1") (pinfunction "SDO_1") (pintype "passive"))
      (node (ref "U2") (pin "6") (pinfunction "GNDIO_6") (pintype "passive"))
      (node (ref "U2") (pin "7") (pinfunction "GND_7") (pintype "passive"))
      (node (ref "U3") (pin "5") (pinfunction "GND_5") (pintype "power_in"))
      (node (ref "U4") (pin "4") (pinfunction "GND_4") (pintype "passive"))
      (node (ref "U5") (pin "6") (pinfunction "GND_6") (pintype "power_in"))
      (node (ref "U6") (pin "1") (pinfunction "GND_1") (pintype "passive"))
      (node (ref "U7") (pin "A5") (pinfunction "~{CS}_A5") (pintype "passive"))
      (node (ref "U7") (pin "C1") (pinfunction "SDO_C1") (pintype "passive"))
      (node (ref "U7") (pin "C5") (pinfunction "GND_C5") (pintype "passive"))
      (node (ref "U7") (pin "E1") (pinfunction "GND_E1") (pintype "passive"))
      (node (ref "U7") (pin "E3") (pinfunction "GND_E3") (pintype "passive"))
      (node (ref "U8") (pin "6") (pinfunction "VSS_6") (pintype "passive"))
      (node (ref "U9") (pin "3") (pinfunction "RES_3") (pintype "passive"))
      (node (ref "U9") (pin "5") (pinfunction "SDO/SAO_5") (pintype "passive"))
      (node (ref "U9") (pin "8") (pinfunction "GND1_8") (pintype "passive"))
      (node (ref "U9") (pin "9") (pinfunction "GND2_9") (pintype "passive"))
    )
    (net (code "45") (name "Net-(C20-Pad2)") (class "Default")
      (node (ref "C20") (pin "2") (pinfunction "2_2") (pintype "passive"))
      (node (ref "C3") (pin "2") (pinfunction "2_2") (pintype "passive"))
      (node (ref "L2") (pin "2") (pinfunction "2_2") (pintype "passive"))
      (node (ref "R6") (pin "2") (pinfunction "2_2") (pintype "passive"))
      (node (ref "SJ4") (pin "1") (pinfunction "1_1") (pintype "passive"))
    )
    (net (code "46") (name "Net-(DL1-PadA)") (class "Default")
      (node (ref "DL1") (pin "A") (pinfunction "A_A") (pintype "passive"))
      (node (ref "R3") (pin "1") (pinfunction "1_1") (pintype "passive"))
    )
    (net (code "47") (name "Net-(DL1-PadC)") (class "Default")
      (node (ref "DL1") (pin "C") (pinfunction "C_C") (pintype "passive"))
      (node (ref "Q1") (pin "D") (pinfunction "D_D") (pintype "passive"))
    )
    (net (code "48") (name "Net-(DL2-PadA)") (class "Default")
      (node (ref "DL2") (pin "A") (pinfunction "A_A") (pintype "passive"))
      (node (ref "R2") (pin "1") (pinfunction "1_1") (pintype "passive"))
    )
    (net (code "49") (name "Net-(DL3-BLUE_C)") (class "Default")
      (node (ref "DL3") (pin "3") (pinfunction "BLUE_C_3") (pintype "passive"))
      (node (ref "R12") (pin "2") (pinfunction "2_2") (pintype "passive"))
    )
    (net (code "50") (name "Net-(DL3-GREEN_C)") (class "Default")
      (node (ref "DL3") (pin "4") (pinfunction "GREEN_C_4") (pintype "passive"))
      (node (ref "R11") (pin "2") (pinfunction "2_2") (pintype "passive"))
    )
    (net (code "51") (name "Net-(DL3-RED_C)") (class "Default")
      (node (ref "DL3") (pin "2") (pinfunction "RED_C_2") (pintype "passive"))
      (node (ref "R7") (pin "2") (pinfunction "2_2") (pintype "passive"))
    )
    (net (code "52") (name "Net-(JP2-VUSB)") (class "Default")
      (node (ref "JP2") (pin "12") (pinfunction "VUSB_12") (pintype "passive"))
      (node (ref "SJ1") (pin "2") (pinfunction "2_2") (pintype "passive"))
      (node (ref "SJ5") (pin "2") (pinfunction "2_2") (pintype "passive"))
    )
    (net (code "53") (name "Net-(U1-NFC1{slash}GPIO28{slash}P0.09)") (class "Default")
      (node (ref "SJ2") (pin "1") (pinfunction "1_1") (pintype "passive"))
      (node (ref "U1") (pin "28") (pinfunction "NFC1/GPIO28/P0.09_28") (pintype "passive"))
    )
    (net (code "54") (name "Net-(U1-NFC2{slash}GPIO29{slash}P0.10)") (class "Default")
      (node (ref "SJ3") (pin "1") (pinfunction "1_1") (pintype "passive"))
      (node (ref "U1") (pin "29") (pinfunction "NFC2/GPIO29/P0.10_29") (pintype "passive"))
    )
    (net (code "55") (name "Net-(U1-TRACED3{slash}GPIO33{slash}P1.09)") (class "Default")
      (node (ref "R2") (pin "2") (pinfunction "2_2") (pintype "passive"))
      (node (ref "U1") (pin "33") (pinfunction "TRACED3/GPIO33/P1.09_33") (pintype "passive"))
    )
    (net (code "56") (name "Net-(U1-VBUS)") (class "Default")
      (node (ref "C10") (pin "1") (pinfunction "1_1") (pintype "passive"))
      (node (ref "L1") (pin "2") (pinfunction "2_2") (pintype "passive"))
      (node (ref "U1") (pin "31") (pinfunction "VBUS_31") (pintype "power_in"))
    )
    (net (code "57") (name "Net-(U5-LDR)") (class "Default")
      (node (ref "U5") (pin "3") (pinfunction "LDR_3") (pintype "passive"))
      (node (ref "U5") (pin "4") (pinfunction "LEDK_4") (pintype "passive"))
    )
    (net (code "58") (name "Net-(U5-VDD)") (class "Default")
      (node (ref "C16") (pin "2") (pinfunction "2_2") (pintype "passive"))
      (node (ref "R15") (pin "1") (pinfunction "1_1") (pintype "passive"))
      (node (ref "U5") (pin "8") (pinfunction "VDD_8") (pintype "power_in"))
    )
    (net (code "59") (name "Net-(U6-BST)") (class "Default")
      (node (ref "C19") (pin "2") (pinfunction "2_2") (pintype "passive"))
      (node (ref "U6") (pin "7") (pinfunction "BST_7") (pintype "passive"))
    )
    (net (code "60") (name "Net-(U6-FB)") (class "Default")
      (node (ref "C20") (pin "1") (pinfunction "1_1") (pintype "passive"))
      (node (ref "R6") (pin "1") (pinfunction "1_1") (pintype "passive"))
      (node (ref "R8") (pin "2") (pinfunction "2_2") (pintype "passive"))
      (node (ref "U6") (pin "5") (pinfunction "FB_5") (pintype "passive"))
    )
    (net (code "61") (name "Net-(U6-SW)") (class "Default")
      (node (ref "C19") (pin "1") (pinfunction "1_1") (pintype "passive"))
      (node (ref "L2") (pin "1") (pinfunction "1_1") (pintype "passive"))
      (node (ref "U6") (pin "8") (pinfunction "SW_8") (pintype "passive"))
    )
    (net (code "62") (name "Net-(U6-VCC)") (class "Default")
      (node (ref "C22") (pin "2") (pinfunction "2_2") (pintype "passive"))
      (node (ref "U6") (pin "4") (pinfunction "VCC_4") (pintype "passive"))
    )
    (net (code "63") (name "Net-(U8-VC)") (class "Default")
      (node (ref "C12") (pin "1") (pinfunction "1_1") (pintype "passive"))
      (node (ref "U8") (pin "3") (pinfunction "VC_3") (pintype "passive"))
    )
    (net (code "64") (name "VDD_ENV") (class "Default")
      (node (ref "C11") (pin "1") (pinfunction "1_1") (pintype "passive"))
      (node (ref "C13") (pin "1") (pinfunction "1_1") (pintype "passive"))
      (node (ref "C14") (pin "1") (pinfunction "1_1") (pintype "passive"))
      (node (ref "C5") (pin "1") (pinfunction "1_1") (pintype "passive"))
      (node (ref "C7") (pin "2") (pinfunction "2_2") (pintype "passive"))
      (node (ref "U1") (pin "49") (pinfunction "QSPID2/GPIO49/P0.22_49") (pintype "passive"))
      (node (ref "U2") (pin "12") (pinfunction "CSB_12") (pintype "passive"))
      (node (ref "U2") (pin "5") (pinfunction "VDDIO_5") (pintype "passive"))
      (node (ref "U2") (pin "8") (pinfunction "VDD_8") (pintype "passive"))
      (node (ref "U7") (pin "A1") (pinfunction "PS_A1") (pintype "passive"))
      (node (ref "U7") (pin "B2") (pinfunction "VDDIO_B2") (pintype "passive"))
      (node (ref "U7") (pin "E5") (pinfunction "VDD_E5") (pintype "passive"))
      (node (ref "U8") (pin "4") (pinfunction "VDD_4") (pintype "passive"))
      (node (ref "U9") (pin "1") (pinfunction "VCCIO_1") (pintype "passive"))
      (node (ref "U9") (pin "10") (pinfunction "VCC_10") (pintype "passive"))
      (node (ref "U9") (pin "6") (pinfunction "CS_6") (pintype "passive"))
    )
    (net (code "65") (name "VIN") (class "Default")
      (node (ref "C23") (pin "2") (pinfunction "2_2") (pintype "passive"))
      (node (ref "C24") (pin "1") (pinfunction "1_1") (pintype "passive"))
      (node (ref "C25") (pin "2") (pinfunction "2_2") (pintype "passive"))
      (node (ref "C4") (pin "2") (pinfunction "2_2") (pintype "passive"))
      (node (ref "D2") (pin "C") (pinfunction "C_C") (pintype "passive"))
      (node (ref "JP2") (pin "15") (pinfunction "VIN_15") (pintype "passive"))
      (node (ref "U6") (pin "2") (pinfunction "IN_2") (pintype "passive"))
      (node (ref "U6") (pin "3") (pinfunction "EN_3") (pintype "passive"))
    )
    (net (code "66") (name "VUSB") (class "Default")
      (node (ref "C6") (pin "1") (pinfunction "1_1") (pintype "passive"))
      (node (ref "D1") (pin "4") (pinfunction "4_4") (pintype "passive"))
      (node (ref "D2") (pin "A") (pinfunction "A_A") (pintype "passive"))
      (node (ref "J1") (pin "1") (pinfunction "1_1") (pintype "passive"))
      (node (ref "L1") (pin "1") (pinfunction "1_1") (pintype "passive"))
      (node (ref "SJ1") (pin "1") (pinfunction "1_1") (pintype "passive"))
      (node (ref "SJ5") (pin "1") (pinfunction "1_1") (pintype "passive"))
    )
    (net (code "67") (name "unconnected-(Fiducial_1-Pad1)") (class "Default")
      (node (ref "Fiducial_1") (pin "1") (pinfunction "1_1") (pintype "passive+no_connect"))
    )
    (net (code "68") (name "unconnected-(Fiducial_2-Pad1)") (class "Default")
      (node (ref "Fiducial_2") (pin "1") (pinfunction "1_1") (pintype "passive+no_connect"))
    )
    (net (code "69") (name "unconnected-(J1-Pad4)") (class "Default")
      (node (ref "J1") (pin "4") (pinfunction "4_4") (pintype "passive+no_connect"))
    )
    (net (code "70") (name "unconnected-(U1-ANT-Pad13)") (class "Default")
      (node (ref "U1") (pin "13") (pinfunction "ANT_13") (pintype "passive+no_connect"))
    )
    (net (code "71") (name "unconnected-(U1-TRACECLK{slash}GPIO45{slash}P0.07-Pad45)") (class "Default")
      (node (ref "U1") (pin "45") (pinfunction "TRACECLK/GPIO45/P0.07_45") (pintype "passive+no_connect"))
    )
    (net (code "72") (name "unconnected-(U2-ASCx-Pad3)") (class "Default")
      (node (ref "U2") (pin "3") (pinfunction "ASCx_3") (pintype "passive+no_connect"))
    )
    (net (code "73") (name "unconnected-(U2-ASDx-Pad2)") (class "Default")
      (node (ref "U2") (pin "2") (pinfunction "ASDx_2") (pintype "passive+no_connect"))
    )
    (net (code "74") (name "unconnected-(U2-OCSB-Pad10)") (class "Default")
      (node (ref "U2") (pin "10") (pinfunction "OCSB_10") (pintype "passive+no_connect"))
    )
    (net (code "75") (name "unconnected-(U2-OSDO-Pad11)") (class "Default")
      (node (ref "U2") (pin "11") (pinfunction "OSDO_11") (pintype "passive+no_connect"))
    )
    (net (code "76") (name "unconnected-(U4-NC-Pad1)") (class "Default")
      (node (ref "U4") (pin "1") (pinfunction "NC_1") (pintype "passive+no_connect"))
    )
    (net (code "77") (name "unconnected-(U4-NC-Pad2)") (class "Default")
      (node (ref "U4") (pin "2") (pinfunction "NC_2") (pintype "passive+no_connect"))
    )
    (net (code "78") (name "unconnected-(U4-NC-Pad3)") (class "Default")
      (node (ref "U4") (pin "3") (pinfunction "NC_3") (pintype "passive+no_connect"))
    )
    (net (code "79") (name "unconnected-(U4-NC-Pad7)") (class "Default")
      (node (ref "U4") (pin "7") (pinfunction "NC_7") (pintype "passive+no_connect"))
    )
    (net (code "80") (name "unconnected-(U4-NC-Pad9)") (class "Default")
      (node (ref "U4") (pin "9") (pinfunction "NC_9") (pintype "passive+no_connect"))
    )
    (net (code "81") (name "unconnected-(U6-PG-Pad6)") (class "Default")
      (node (ref "U6") (pin "6") (pinfunction "PG_6") (pintype "passive+no_connect"))
    )
    (net (code "82") (name "unconnected-(U7-DRDY-PadD4)") (class "Default")
      (node (ref "U7") (pin "D4") (pinfunction "DRDY_D4") (pintype "passive+no_connect"))
    )
    (net (code "83") (name "unconnected-(U7-INT-PadD2)") (class "Default")
      (node (ref "U7") (pin "D2") (pinfunction "INT_D2") (pintype "passive+no_connect"))
    )
    (net (code "84") (name "unconnected-(U8-NC-Pad5)") (class "Default")
      (node (ref "U8") (pin "5") (pinfunction "NC_5") (pintype "passive+no_connect"))
    )
  )
)
